# P11-CAMERA_AVIN.net
KiCad netlist of a schematic drawn in Altium Designer
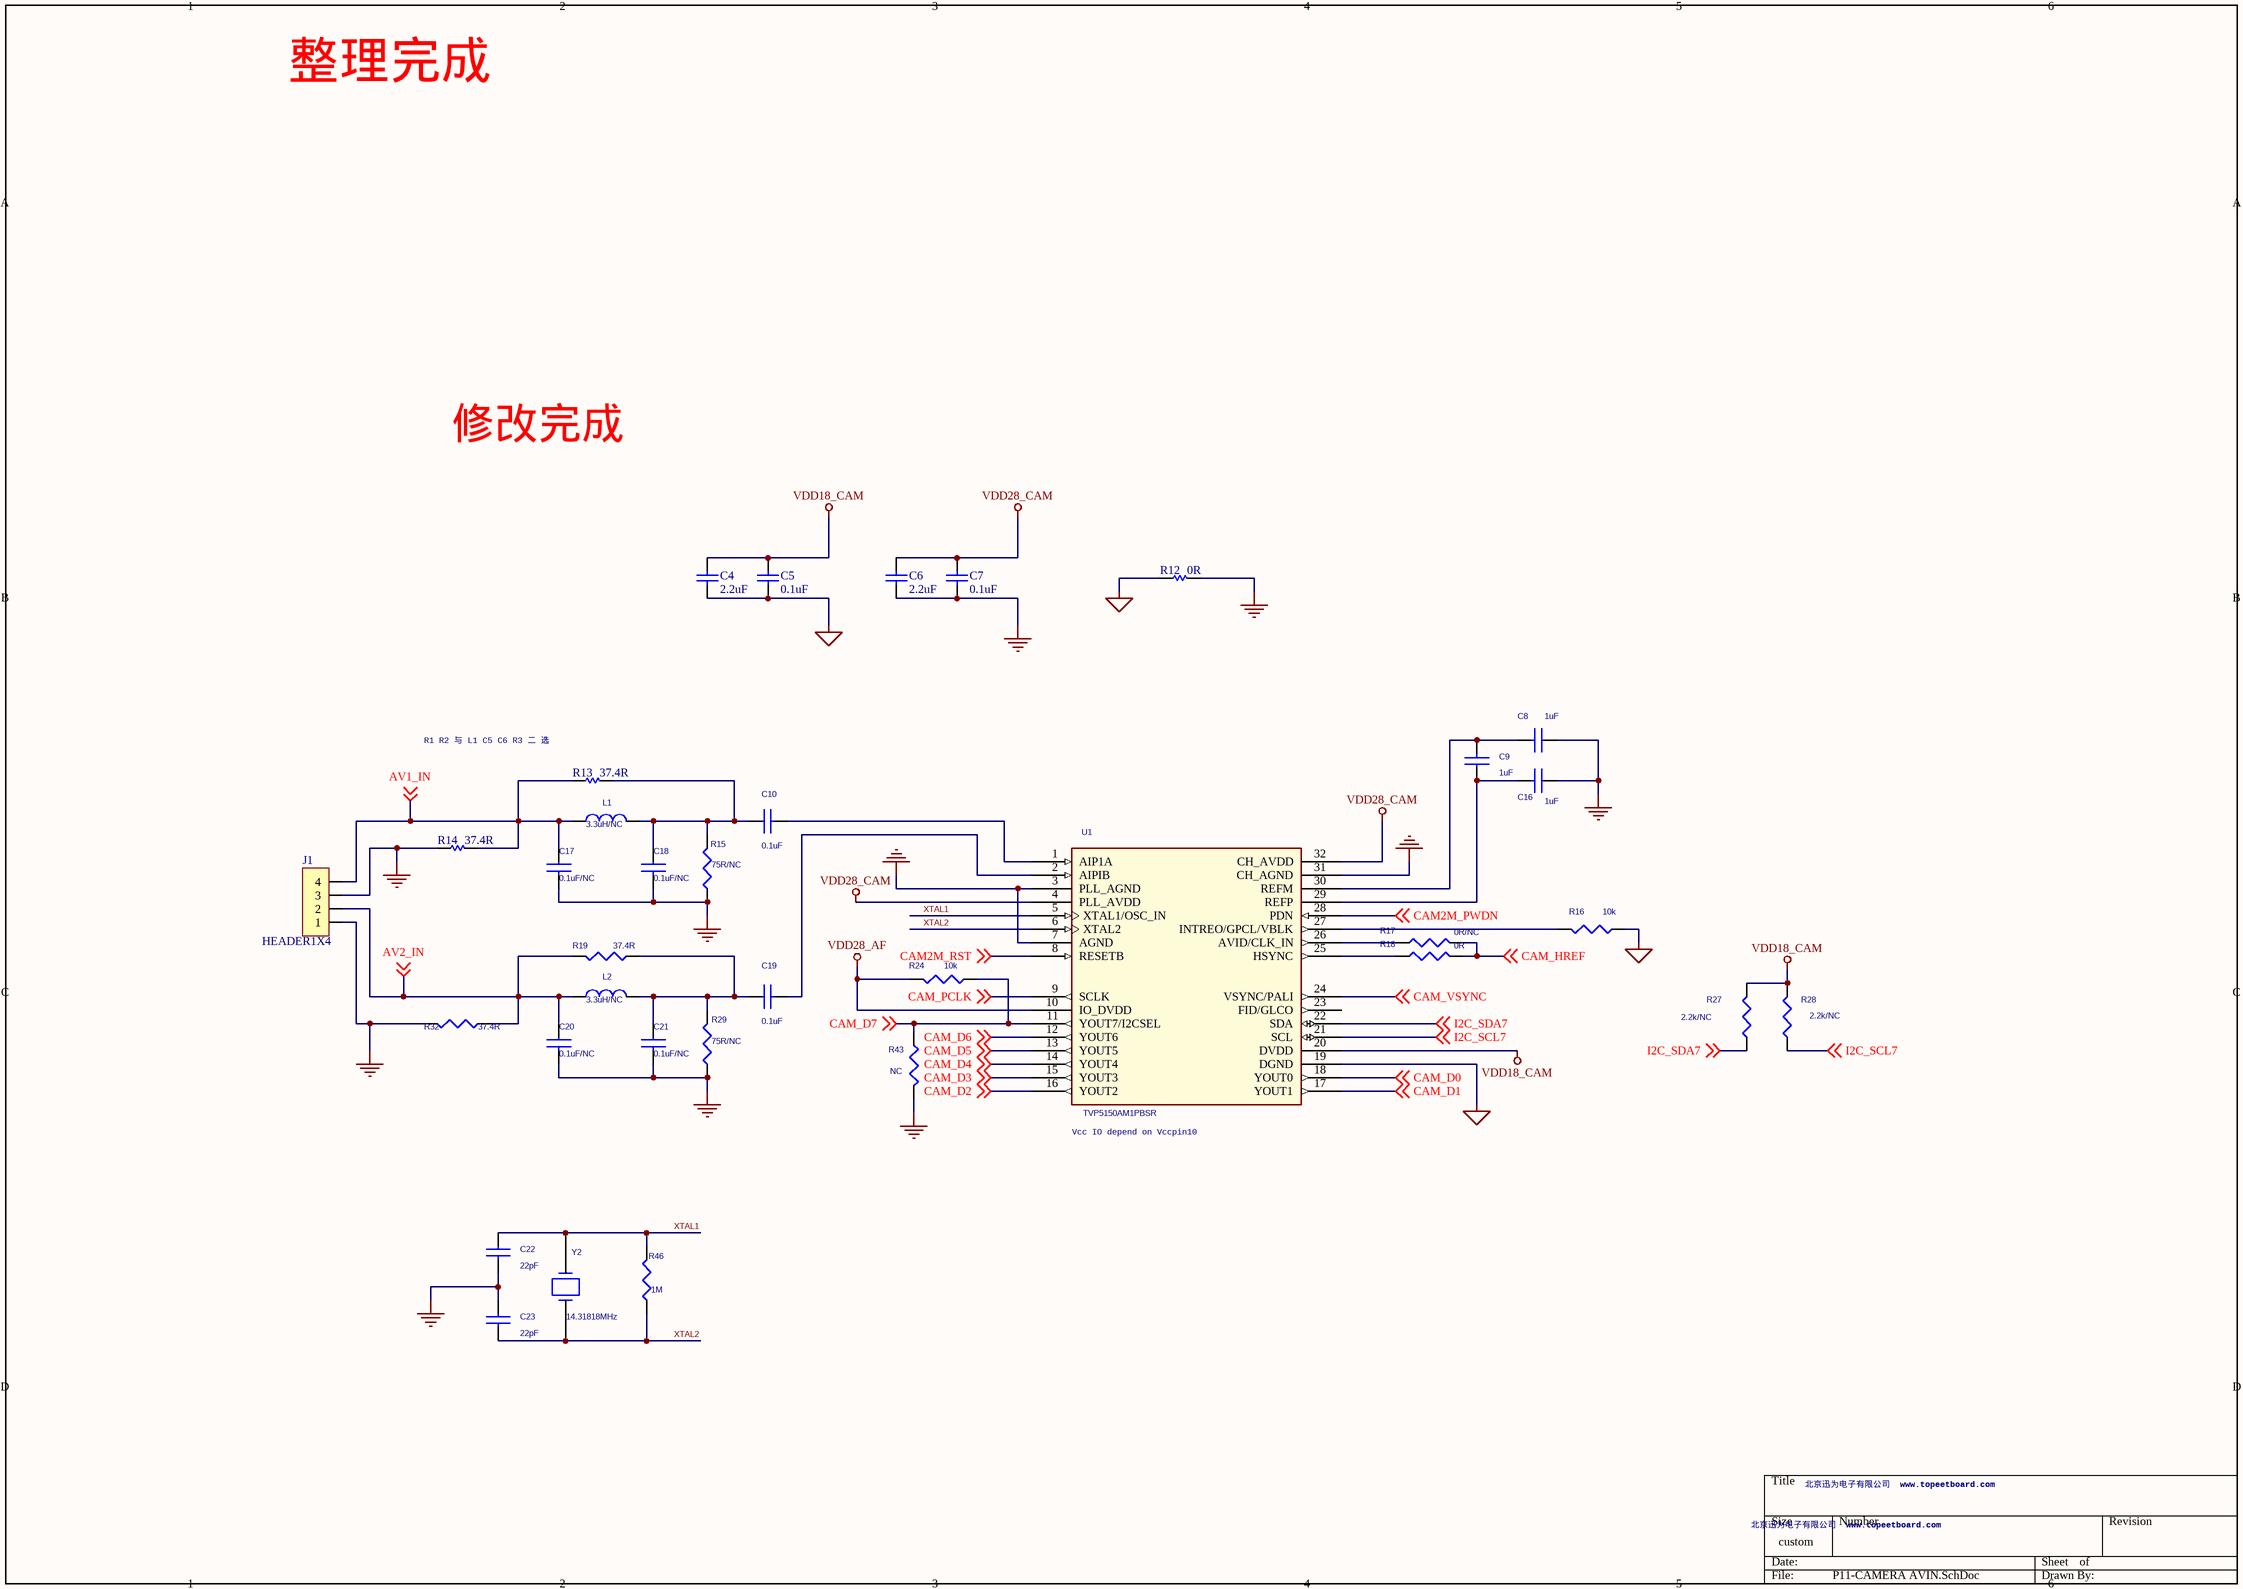
[diagram p0: P11-CAMERA AVIN.SchDoc]

(export (version "E")
  (design (tool "Eeschema 10.0.6"))
  (components
    (comp (ref "C4") (value "2.2uF") (footprint "C0603-S") (libsource (lib "RLCYDF") (part "Cap Semi")))
    (comp (ref "C5") (value "0.1uF") (footprint "C0603-S") (libsource (lib "RLCYDF") (part "Cap Semi")))
    (comp (ref "C6") (value "2.2uF") (footprint "C0603-S") (libsource (lib "RLCYDF") (part "Cap Semi")))
    (comp (ref "C7") (value "0.1uF") (footprint "C0603-S") (libsource (lib "RLCYDF") (part "Cap Semi")))
    (comp (ref "C8") (value "1uF") (footprint "C0603-S") (libsource (lib "*") (part "C0603_0")))
    (comp (ref "C9") (value "1uF") (footprint "C0603-S") (libsource (lib "*") (part "C0603_0")))
    (comp (ref "C10") (value "0.1uF") (footprint "C0603-S") (libsource (lib "*") (part "C0603_0")))
    (comp (ref "C16") (value "1uF") (footprint "C0603-S") (libsource (lib "*") (part "C0603_0")))
    (comp (ref "C17") (value "0.1uF/NC") (footprint "C0603-S") (libsource (lib "*") (part "C0603_0")))
    (comp (ref "C18") (value "0.1uF/NC") (footprint "C0603-S") (libsource (lib "*") (part "C0603_0")))
    (comp (ref "C19") (value "0.1uF") (footprint "C0603-S") (libsource (lib "*") (part "C0603_0")))
    (comp (ref "C20") (value "0.1uF/NC") (footprint "C0603-S") (libsource (lib "*") (part "C0603_0")))
    (comp (ref "C21") (value "0.1uF/NC") (footprint "C0603-S") (libsource (lib "*") (part "C0603_0")))
    (comp (ref "C22") (value "22pF") (footprint "C0603-s") (libsource (lib "*") (part "C1005")))
    (comp (ref "C23") (value "22pF") (footprint "C0603-s") (libsource (lib "*") (part "C1005")))
    (comp (ref "J1")
      (value "HEADER1X4")
      (footprint "HD1X4-2.00")
      (libsource (lib "Connector Class") (part "HEADER1X4"))
    )
    (comp (ref "L1") (value "3.3uH/NC") (footprint "L4X4-S") (libsource (lib "*") (part "LQH32C_0")))
    (comp (ref "L2") (value "3.3uH/NC") (footprint "L4X4-S") (libsource (lib "*") (part "LQH32C_0")))
    (comp (ref "R12") (value "0R") (footprint "R0603-S") (libsource (lib "RLCYDF") (part "Res")))
    (comp (ref "R13") (value "37.4R") (footprint "R0603-S") (libsource (lib "RLCYDF") (part "Res")))
    (comp (ref "R14") (value "37.4R") (footprint "R0603-S") (libsource (lib "RLCYDF") (part "Res")))
    (comp (ref "R15") (value "75R/NC") (footprint "R0603-S") (libsource (lib "*") (part "R0603")))
    (comp (ref "R16") (value "10k") (footprint "R0603-S") (libsource (lib "*") (part "R0603")))
    (comp (ref "R17") (value "0R/NC") (footprint "R0603-S") (libsource (lib "*") (part "R0603")))
    (comp (ref "R18") (value "0R") (footprint "R0603-S") (libsource (lib "*") (part "R0603")))
    (comp (ref "R19") (value "37.4R") (footprint "R0603-S") (libsource (lib "*") (part "R0603")))
    (comp (ref "R24") (value "10k") (footprint "R0603-S") (libsource (lib "*") (part "R0603")))
    (comp (ref "R27") (value "2.2k/NC") (footprint "R0603-S") (libsource (lib "*") (part "R0603")))
    (comp (ref "R28") (value "2.2k/NC") (footprint "R0603-S") (libsource (lib "*") (part "R0603")))
    (comp (ref "R29") (value "75R/NC") (footprint "R0603-S") (libsource (lib "*") (part "R0603")))
    (comp (ref "R32") (value "37.4R") (footprint "R0603-S") (libsource (lib "*") (part "R0603")))
    (comp (ref "R43") (value "NC") (footprint "R0603-S") (libsource (lib "*") (part "R0603")))
    (comp (ref "R46") (value "1M") (footprint "R0603-S") (libsource (lib "*") (part "R0603")))
    (comp (ref "U1") (value "TVP5150AM1PBSR") (libsource (lib "*") (part "TVP5151")))
    (comp (ref "Y2") (value "14.31818MHz") (libsource (lib "*") (part "XM/SM")))
  )
  (nets
    (net (code "1") (name "/XTAL1") (class "Default")
      (node (ref "C22") (pin "1") (pinfunction "1_1") (pintype "passive"))
      (node (ref "R46") (pin "2") (pinfunction "2_2") (pintype "passive"))
      (node (ref "U1") (pin "5") (pinfunction "XTAL1/OSC_IN_5") (pintype "input"))
      (node (ref "Y2") (pin "2") (pinfunction "2_2") (pintype "passive"))
    )
    (net (code "2") (name "/XTAL2") (class "Default")
      (node (ref "C23") (pin "2") (pinfunction "2_2") (pintype "passive"))
      (node (ref "R46") (pin "1") (pinfunction "1_1") (pintype "passive"))
      (node (ref "U1") (pin "6") (pinfunction "XTAL2_6") (pintype "input"))
      (node (ref "Y2") (pin "1") (pinfunction "1_1") (pintype "passive"))
    )
    (net (code "3") (name "AGND") (class "Default")
      (node (ref "C4") (pin "1") (pinfunction "1_1") (pintype "passive"))
      (node (ref "C5") (pin "1") (pinfunction "1_1") (pintype "passive"))
      (node (ref "R12") (pin "1") (pinfunction "1_1") (pintype "passive"))
      (node (ref "R16") (pin "1") (pinfunction "1_1") (pintype "passive"))
      (node (ref "U1") (pin "19") (pinfunction "DGND_19") (pintype "power_in"))
    )
    (net (code "4") (name "AV1_IN") (class "Default")
      (node (ref "C17") (pin "1") (pinfunction "1_1") (pintype "passive"))
      (node (ref "J1") (pin "4") (pinfunction "4_4") (pintype "passive"))
      (node (ref "L1") (pin "1") (pinfunction "1_1") (pintype "passive"))
      (node (ref "R13") (pin "1") (pinfunction "1_1") (pintype "passive"))
      (node (ref "R14") (pin "2") (pinfunction "2_2") (pintype "passive"))
    )
    (net (code "5") (name "AV2_IN") (class "Default")
      (node (ref "C20") (pin "1") (pinfunction "1_1") (pintype "passive"))
      (node (ref "J1") (pin "2") (pinfunction "2_2") (pintype "passive"))
      (node (ref "L2") (pin "1") (pinfunction "1_1") (pintype "passive"))
      (node (ref "R19") (pin "2") (pinfunction "2_2") (pintype "passive"))
      (node (ref "R32") (pin "1") (pinfunction "1_1") (pintype "passive"))
    )
    (net (code "6") (name "CAM2M_PWDN") (class "Default")
      (node (ref "U1") (pin "28") (pinfunction "PDN_28") (pintype "input"))
    )
    (net (code "7") (name "CAM2M_RST") (class "Default")
      (node (ref "U1") (pin "8") (pinfunction "RESETB_8") (pintype "input"))
    )
    (net (code "8") (name "CAM_D0") (class "Default")
      (node (ref "U1") (pin "18") (pinfunction "YOUT0_18") (pintype "output"))
    )
    (net (code "9") (name "CAM_D1") (class "Default")
      (node (ref "U1") (pin "17") (pinfunction "YOUT1_17") (pintype "output"))
    )
    (net (code "10") (name "CAM_D2") (class "Default")
      (node (ref "U1") (pin "16") (pinfunction "YOUT2_16") (pintype "output"))
    )
    (net (code "11") (name "CAM_D3") (class "Default")
      (node (ref "U1") (pin "15") (pinfunction "YOUT3_15") (pintype "output"))
    )
    (net (code "12") (name "CAM_D4") (class "Default")
      (node (ref "U1") (pin "14") (pinfunction "YOUT4_14") (pintype "output"))
    )
    (net (code "13") (name "CAM_D5") (class "Default")
      (node (ref "U1") (pin "13") (pinfunction "YOUT5_13") (pintype "output"))
    )
    (net (code "14") (name "CAM_D6") (class "Default")
      (node (ref "U1") (pin "12") (pinfunction "YOUT6_12") (pintype "output"))
    )
    (net (code "15") (name "CAM_D7") (class "Default")
      (node (ref "R24") (pin "1") (pinfunction "1_1") (pintype "passive"))
      (node (ref "R43") (pin "1") (pinfunction "1_1") (pintype "passive"))
      (node (ref "U1") (pin "11") (pinfunction "YOUT7/I2CSEL_11") (pintype "output"))
    )
    (net (code "16") (name "CAM_HREF") (class "Default")
      (node (ref "R17") (pin "2") (pinfunction "2_2") (pintype "passive"))
      (node (ref "R18") (pin "2") (pinfunction "2_2") (pintype "passive"))
    )
    (net (code "17") (name "CAM_PCLK") (class "Default")
      (node (ref "U1") (pin "9") (pinfunction "SCLK_9") (pintype "output"))
    )
    (net (code "18") (name "CAM_VSYNC") (class "Default")
      (node (ref "U1") (pin "24") (pinfunction "VSYNC/PALI_24") (pintype "output"))
    )
    (net (code "19") (name "GND") (class "Default")
      (node (ref "C16") (pin "1") (pinfunction "1_1") (pintype "passive"))
      (node (ref "C17") (pin "2") (pinfunction "2_2") (pintype "passive"))
      (node (ref "C18") (pin "2") (pinfunction "2_2") (pintype "passive"))
      (node (ref "C20") (pin "2") (pinfunction "2_2") (pintype "passive"))
      (node (ref "C21") (pin "2") (pinfunction "2_2") (pintype "passive"))
      (node (ref "C22") (pin "2") (pinfunction "2_2") (pintype "passive"))
      (node (ref "C23") (pin "1") (pinfunction "1_1") (pintype "passive"))
      (node (ref "C6") (pin "1") (pinfunction "1_1") (pintype "passive"))
      (node (ref "C7") (pin "1") (pinfunction "1_1") (pintype "passive"))
      (node (ref "C8") (pin "1") (pinfunction "1_1") (pintype "passive"))
      (node (ref "J1") (pin "1") (pinfunction "1_1") (pintype "passive"))
      (node (ref "J1") (pin "3") (pinfunction "3_3") (pintype "passive"))
      (node (ref "R12") (pin "2") (pinfunction "2_2") (pintype "passive"))
      (node (ref "R14") (pin "1") (pinfunction "1_1") (pintype "passive"))
      (node (ref "R15") (pin "1") (pinfunction "1_1") (pintype "passive"))
      (node (ref "R29") (pin "1") (pinfunction "1_1") (pintype "passive"))
      (node (ref "R32") (pin "2") (pinfunction "2_2") (pintype "passive"))
      (node (ref "R43") (pin "2") (pinfunction "2_2") (pintype "passive"))
      (node (ref "U1") (pin "3") (pinfunction "PLL_AGND_3") (pintype "power_in"))
      (node (ref "U1") (pin "31") (pinfunction "CH_AGND_31") (pintype "power_in"))
      (node (ref "U1") (pin "7") (pinfunction "AGND_7") (pintype "power_in"))
    )
    (net (code "20") (name "I2C_SCL7") (class "Default")
      (node (ref "R28") (pin "1") (pinfunction "1_1") (pintype "passive"))
      (node (ref "U1") (pin "21") (pinfunction "SCL_21") (pintype "bidirectional"))
    )
    (net (code "21") (name "I2C_SDA7") (class "Default")
      (node (ref "R27") (pin "1") (pinfunction "1_1") (pintype "passive"))
      (node (ref "U1") (pin "22") (pinfunction "SDA_22") (pintype "bidirectional"))
    )
    (net (code "22") (name "Net-(C10-Pad1)") (class "Default")
      (node (ref "C10") (pin "1") (pinfunction "1_1") (pintype "passive"))
      (node (ref "C18") (pin "1") (pinfunction "1_1") (pintype "passive"))
      (node (ref "L1") (pin "2") (pinfunction "2_2") (pintype "passive"))
      (node (ref "R13") (pin "2") (pinfunction "2_2") (pintype "passive"))
      (node (ref "R15") (pin "2") (pinfunction "2_2") (pintype "passive"))
    )
    (net (code "23") (name "Net-(C19-Pad1)") (class "Default")
      (node (ref "C19") (pin "1") (pinfunction "1_1") (pintype "passive"))
      (node (ref "C21") (pin "1") (pinfunction "1_1") (pintype "passive"))
      (node (ref "L2") (pin "2") (pinfunction "2_2") (pintype "passive"))
      (node (ref "R19") (pin "1") (pinfunction "1_1") (pintype "passive"))
      (node (ref "R29") (pin "2") (pinfunction "2_2") (pintype "passive"))
    )
    (net (code "24") (name "Net-(U1-AIP1A)") (class "Default")
      (node (ref "C10") (pin "2") (pinfunction "2_2") (pintype "passive"))
      (node (ref "U1") (pin "1") (pinfunction "AIP1A_1") (pintype "input"))
    )
    (net (code "25") (name "Net-(U1-AIPIB)") (class "Default")
      (node (ref "C19") (pin "2") (pinfunction "2_2") (pintype "passive"))
      (node (ref "U1") (pin "2") (pinfunction "AIPIB_2") (pintype "input"))
    )
    (net (code "26") (name "Net-(U1-AVID{slash}CLK_IN)") (class "Default")
      (node (ref "R17") (pin "1") (pinfunction "1_1") (pintype "passive"))
      (node (ref "U1") (pin "26") (pinfunction "AVID/CLK_IN_26") (pintype "output"))
    )
    (net (code "27") (name "Net-(U1-HSYNC)") (class "Default")
      (node (ref "R18") (pin "1") (pinfunction "1_1") (pintype "passive"))
      (node (ref "U1") (pin "25") (pinfunction "HSYNC_25") (pintype "output"))
    )
    (net (code "28") (name "Net-(U1-INTREO{slash}GPCL{slash}VBLK)") (class "Default")
      (node (ref "R16") (pin "2") (pinfunction "2_2") (pintype "passive"))
      (node (ref "U1") (pin "27") (pinfunction "INTREO/GPCL/VBLK_27") (pintype "output"))
    )
    (net (code "29") (name "Net-(U1-REFM)") (class "Default")
      (node (ref "C8") (pin "2") (pinfunction "2_2") (pintype "passive"))
      (node (ref "C9") (pin "2") (pinfunction "2_2") (pintype "passive"))
      (node (ref "U1") (pin "30") (pinfunction "REFM_30") (pintype "passive"))
    )
    (net (code "30") (name "Net-(U1-REFP)") (class "Default")
      (node (ref "C16") (pin "2") (pinfunction "2_2") (pintype "passive"))
      (node (ref "C9") (pin "1") (pinfunction "1_1") (pintype "passive"))
      (node (ref "U1") (pin "29") (pinfunction "REFP_29") (pintype "passive"))
    )
    (net (code "31") (name "VDD18_CAM") (class "Default")
      (node (ref "C4") (pin "2") (pinfunction "2_2") (pintype "passive"))
      (node (ref "C5") (pin "2") (pinfunction "2_2") (pintype "passive"))
      (node (ref "R27") (pin "2") (pinfunction "2_2") (pintype "passive"))
      (node (ref "R28") (pin "2") (pinfunction "2_2") (pintype "passive"))
      (node (ref "U1") (pin "20") (pinfunction "DVDD_20") (pintype "power_in"))
    )
    (net (code "32") (name "VDD28_AF") (class "Default")
      (node (ref "R24") (pin "2") (pinfunction "2_2") (pintype "passive"))
      (node (ref "U1") (pin "10") (pinfunction "IO_DVDD_10") (pintype "power_in"))
    )
    (net (code "33") (name "VDD28_CAM") (class "Default")
      (node (ref "C6") (pin "2") (pinfunction "2_2") (pintype "passive"))
      (node (ref "C7") (pin "2") (pinfunction "2_2") (pintype "passive"))
      (node (ref "U1") (pin "32") (pinfunction "CH_AVDD_32") (pintype "power_in"))
      (node (ref "U1") (pin "4") (pinfunction "PLL_AVDD_4") (pintype "power_in"))
    )
    (net (code "34") (name "unconnected-(U1-FID{slash}GLCO-Pad23)") (class "Default")
      (node (ref "U1") (pin "23") (pinfunction "FID/GLCO_23") (pintype "output"))
    )
  )
)
